# Reefing-Radio_MCU.net
KiCad netlist of a schematic drawn in Altium Designer
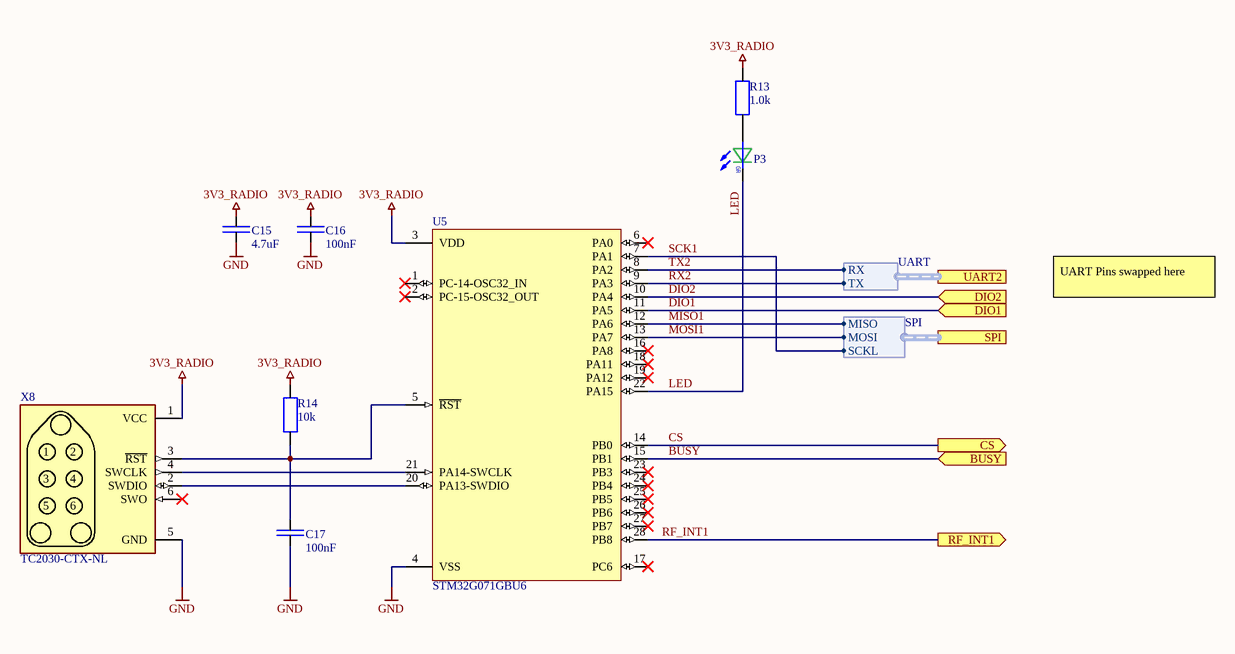
[diagram p0: Reefing-Radio_MCU.SchDoc]

(export (version "E")
  (design (tool "Eeschema 10.0.6"))
  (components
    (comp (ref "C15")
      (value "4.7uF")
      (footprint "SMD Keramikkondensator 0402")
      (description "SMD Ceramic Capacitor E6")
      (libsource (lib "CATS-EUROC") (part "E6 - 4.7uF"))
    )
    (comp (ref "C16")
      (value "100nF")
      (footprint "SMD Keramikkondensator 0402")
      (description "SMD Ceramic Capacitor E6")
      (libsource (lib "CATS-EUROC") (part "E6 - 100nF"))
    )
    (comp (ref "C17")
      (value "100nF")
      (footprint "SMD Keramikkondensator 0402")
      (description "SMD Ceramic Capacitor E6")
      (libsource (lib "CATS-EUROC") (part "E6 - 100nF"))
    )
    (comp (ref "P3")
      (value "LED")
      (footprint "SMD LED 0603")
      (description "Color LED")
      (libsource (lib "Diodes") (part "LED"))
    )
    (comp (ref "R13")
      (value "1.0k")
      (footprint "SMD Widerstand 0402")
      (description "SMD Chip Resistor E24")
      (libsource (lib "CATS-EUROC") (part "E24 - 1.0k"))
    )
    (comp (ref "R14")
      (value "10k")
      (footprint "SMD Widerstand 0402")
      (description "SMD Chip Resistor E24")
      (libsource (lib "CATS-EUROC") (part "E24 - 10k"))
    )
    (comp (ref "U5")
      (value "STM32G071GBU6")
      (footprint "SMD IC QFN-28 4x4 0.5 Pitch")
      (description "ARM® Cortex®-M0+ series Microcontroller IC 32-Bit 64MHz 128KB (128K x 8) FLASH 28-UFQFPN (4x4)")
      (libsource (lib "Microcontrollers") (part "STM32G071GBU6"))
    )
    (comp (ref "X8")
      (value "TC2030-CTX-NL")
      (footprint "SMD Connector TC2030")
      (description "Tag-Connect for ARM-Cortex (6-Pin)")
      (libsource (lib "Connectors") (part "TC2030-CTX-NL"))
    )
  )
  (nets
    (net (code "3") (name "/BUSY") (class "Default")
      (node (ref "U5") (pin "15") (pinfunction "PB1_15") (pintype "bidirectional"))
    )
    (net (code "4") (name "/CS") (class "Default")
      (node (ref "U5") (pin "14") (pinfunction "PB0_14") (pintype "bidirectional"))
    )
    (net (code "5") (name "/DIO1") (class "Default")
      (node (ref "U5") (pin "11") (pinfunction "PA5_11") (pintype "bidirectional"))
    )
    (net (code "6") (name "/DIO2") (class "Default")
      (node (ref "U5") (pin "10") (pinfunction "PA4_10") (pintype "bidirectional"))
    )
    (net (code "7") (name "/LED") (class "Default")
      (node (ref "P3") (pin "K") (pinfunction "K_K") (pintype "passive"))
      (node (ref "U5") (pin "22") (pinfunction "PA15_22") (pintype "bidirectional"))
    )
    (net (code "8") (name "/MISO1") (class "Default")
      (node (ref "U5") (pin "12") (pinfunction "PA6_12") (pintype "bidirectional"))
    )
    (net (code "9") (name "/MOSI1") (class "Default")
      (node (ref "U5") (pin "13") (pinfunction "PA7_13") (pintype "bidirectional"))
    )
    (net (code "10") (name "/RF_INT1") (class "Default")
      (node (ref "U5") (pin "28") (pinfunction "PB8_28") (pintype "bidirectional"))
    )
    (net (code "11") (name "/RX2") (class "Default")
      (node (ref "U5") (pin "9") (pinfunction "PA3_9") (pintype "bidirectional"))
    )
    (net (code "12") (name "/SCK1") (class "Default")
      (node (ref "U5") (pin "7") (pinfunction "PA1_7") (pintype "bidirectional"))
    )
    (net (code "13") (name "/TX2") (class "Default")
      (node (ref "U5") (pin "8") (pinfunction "PA2_8") (pintype "bidirectional"))
    )
    (net (code "16") (name "3V3_RADIO") (class "Default")
      (node (ref "C15") (pin "2") (pinfunction "2_2") (pintype "passive"))
      (node (ref "C16") (pin "2") (pinfunction "2_2") (pintype "passive"))
      (node (ref "R13") (pin "2") (pinfunction "2_2") (pintype "passive"))
      (node (ref "R14") (pin "2") (pinfunction "2_2") (pintype "passive"))
      (node (ref "U5") (pin "3") (pinfunction "VDD_3") (pintype "passive"))
      (node (ref "X8") (pin "1") (pinfunction "VCC_1") (pintype "power_in"))
    )
    (net (code "17") (name "GND") (class "Default")
      (node (ref "C15") (pin "1") (pinfunction "1_1") (pintype "passive"))
      (node (ref "C16") (pin "1") (pinfunction "1_1") (pintype "passive"))
      (node (ref "C17") (pin "1") (pinfunction "1_1") (pintype "passive"))
      (node (ref "U5") (pin "4") (pinfunction "VSS_4") (pintype "passive"))
      (node (ref "X8") (pin "5") (pinfunction "GND_5") (pintype "power_in"))
    )
    (net (code "18") (name "Net-(P3-PadA)") (class "Default")
      (node (ref "P3") (pin "A") (pinfunction "A_A") (pintype "passive"))
      (node (ref "R13") (pin "1") (pinfunction "1_1") (pintype "passive"))
    )
    (net (code "19") (name "Net-(U5-PA13-SWDIO)") (class "Default")
      (node (ref "U5") (pin "20") (pinfunction "PA13-SWDIO_20") (pintype "bidirectional"))
      (node (ref "X8") (pin "2") (pinfunction "SWDIO_2") (pintype "bidirectional"))
    )
    (net (code "20") (name "Net-(U5-PA14-SWCLK)") (class "Default")
      (node (ref "U5") (pin "21") (pinfunction "PA14-SWCLK_21") (pintype "input"))
      (node (ref "X8") (pin "4") (pinfunction "SWCLK_4") (pintype "output"))
    )
    (net (code "21") (name "Net-(U5-~{RST})") (class "Default")
      (node (ref "C17") (pin "2") (pinfunction "2_2") (pintype "passive"))
      (node (ref "R14") (pin "1") (pinfunction "1_1") (pintype "passive"))
      (node (ref "U5") (pin "5") (pinfunction "~{RST}_5") (pintype "input"))
      (node (ref "X8") (pin "3") (pinfunction "~{RST}_3") (pintype "output"))
    )
    (net (code "22") (name "unconnected-(U5-PA0-Pad6)") (class "Default")
      (node (ref "U5") (pin "6") (pinfunction "PA0_6") (pintype "bidirectional+no_connect"))
    )
    (net (code "23") (name "unconnected-(U5-PA8-Pad16)") (class "Default")
      (node (ref "U5") (pin "16") (pinfunction "PA8_16") (pintype "bidirectional+no_connect"))
    )
    (net (code "24") (name "unconnected-(U5-PA11-Pad18)") (class "Default")
      (node (ref "U5") (pin "18") (pinfunction "PA11_18") (pintype "bidirectional+no_connect"))
    )
    (net (code "25") (name "unconnected-(U5-PA12-Pad19)") (class "Default")
      (node (ref "U5") (pin "19") (pinfunction "PA12_19") (pintype "bidirectional+no_connect"))
    )
    (net (code "26") (name "unconnected-(U5-PB3-Pad23)") (class "Default")
      (node (ref "U5") (pin "23") (pinfunction "PB3_23") (pintype "bidirectional+no_connect"))
    )
    (net (code "27") (name "unconnected-(U5-PB4-Pad24)") (class "Default")
      (node (ref "U5") (pin "24") (pinfunction "PB4_24") (pintype "bidirectional+no_connect"))
    )
    (net (code "28") (name "unconnected-(U5-PB5-Pad25)") (class "Default")
      (node (ref "U5") (pin "25") (pinfunction "PB5_25") (pintype "bidirectional+no_connect"))
    )
    (net (code "29") (name "unconnected-(U5-PB6-Pad26)") (class "Default")
      (node (ref "U5") (pin "26") (pinfunction "PB6_26") (pintype "bidirectional+no_connect"))
    )
    (net (code "30") (name "unconnected-(U5-PB7-Pad27)") (class "Default")
      (node (ref "U5") (pin "27") (pinfunction "PB7_27") (pintype "bidirectional+no_connect"))
    )
    (net (code "31") (name "unconnected-(U5-PC-14-OSC32_IN-Pad1)") (class "Default")
      (node (ref "U5") (pin "1") (pinfunction "PC-14-OSC32_IN_1") (pintype "bidirectional+no_connect"))
    )
    (net (code "32") (name "unconnected-(U5-PC-15-OSC32_OUT-Pad2)") (class "Default")
      (node (ref "U5") (pin "2") (pinfunction "PC-15-OSC32_OUT_2") (pintype "bidirectional+no_connect"))
    )
    (net (code "33") (name "unconnected-(U5-PC6-Pad17)") (class "Default")
      (node (ref "U5") (pin "17") (pinfunction "PC6_17") (pintype "bidirectional+no_connect"))
    )
    (net (code "34") (name "unconnected-(X8-SWO-Pad6)") (class "Default")
      (node (ref "X8") (pin "6") (pinfunction "SWO_6") (pintype "input+no_connect"))
    )
  )
)
